# main.net
KiCad netlist of a schematic drawn in EAGLE
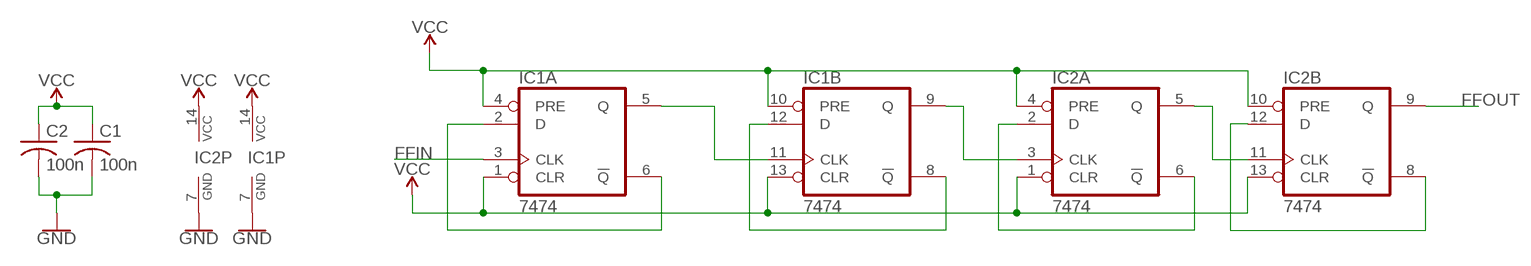
[diagram p0: schematic, sheet 1]

(export (version "E")
  (design (tool "Eeschema 10.0.6"))
  (components
    (comp (ref "C1")
      (value "100n")
      (footprint "eagle-import:C0603")
      (libsource (lib "eagle-import") (part "C-USC0603"))
    )
    (comp (ref "C2")
      (value "100n")
      (footprint "eagle-import:C0603")
      (libsource (lib "eagle-import") (part "C-USC0603"))
    )
    (comp (ref "IC1")
      (value "7474")
      (footprint "eagle-import:TSSOP14")
      (libsource (lib "eagle-import") (part "7474"))
    )
    (comp (ref "IC2")
      (value "7474")
      (footprint "eagle-import:TSSOP14")
      (libsource (lib "eagle-import") (part "7474"))
    )
  )
  (nets
    (net (code "1") (name "/FFIN") (class "Default")
      (node (ref "IC1") (pin "3") (pinfunction "CLK_3") (pintype "input"))
    )
    (net (code "2") (name "/FFOUT") (class "Default")
      (node (ref "IC2") (pin "9") (pinfunction "Q_9") (pintype "output"))
    )
    (net (code "3") (name "GND") (class "Default")
      (node (ref "C1") (pin "2") (pinfunction "2_2") (pintype "passive"))
      (node (ref "C2") (pin "2") (pinfunction "2_2") (pintype "passive"))
      (node (ref "IC1") (pin "7") (pinfunction "GND_7") (pintype "power_in"))
      (node (ref "IC2") (pin "7") (pinfunction "GND_7") (pintype "power_in"))
    )
    (net (code "4") (name "Net-(IC1A-D)") (class "Default")
      (node (ref "IC1") (pin "2") (pinfunction "D_2") (pintype "input"))
      (node (ref "IC1") (pin "6") (pinfunction "~{Q}_6") (pintype "output"))
    )
    (net (code "5") (name "Net-(IC1A-Q)") (class "Default")
      (node (ref "IC1") (pin "11") (pinfunction "CLK_11") (pintype "input"))
      (node (ref "IC1") (pin "5") (pinfunction "Q_5") (pintype "output"))
    )
    (net (code "6") (name "Net-(IC1B-D)") (class "Default")
      (node (ref "IC1") (pin "12") (pinfunction "D_12") (pintype "input"))
      (node (ref "IC1") (pin "8") (pinfunction "~{Q}_8") (pintype "output"))
    )
    (net (code "7") (name "Net-(IC1B-Q)") (class "Default")
      (node (ref "IC1") (pin "9") (pinfunction "Q_9") (pintype "output"))
      (node (ref "IC2") (pin "3") (pinfunction "CLK_3") (pintype "input"))
    )
    (net (code "8") (name "Net-(IC2A-D)") (class "Default")
      (node (ref "IC2") (pin "2") (pinfunction "D_2") (pintype "input"))
      (node (ref "IC2") (pin "6") (pinfunction "~{Q}_6") (pintype "output"))
    )
    (net (code "9") (name "Net-(IC2A-Q)") (class "Default")
      (node (ref "IC2") (pin "11") (pinfunction "CLK_11") (pintype "input"))
      (node (ref "IC2") (pin "5") (pinfunction "Q_5") (pintype "output"))
    )
    (net (code "10") (name "Net-(IC2B-D)") (class "Default")
      (node (ref "IC2") (pin "12") (pinfunction "D_12") (pintype "input"))
      (node (ref "IC2") (pin "8") (pinfunction "~{Q}_8") (pintype "output"))
    )
    (net (code "11") (name "VCC") (class "Default")
      (node (ref "C1") (pin "1") (pinfunction "1_1") (pintype "passive"))
      (node (ref "C2") (pin "1") (pinfunction "1_1") (pintype "passive"))
      (node (ref "IC1") (pin "1") (pinfunction "CLR_1") (pintype "input"))
      (node (ref "IC1") (pin "10") (pinfunction "PRE_10") (pintype "input"))
      (node (ref "IC1") (pin "13") (pinfunction "CLR_13") (pintype "input"))
      (node (ref "IC1") (pin "14") (pinfunction "VCC_14") (pintype "power_in"))
      (node (ref "IC1") (pin "4") (pinfunction "PRE_4") (pintype "input"))
      (node (ref "IC2") (pin "1") (pinfunction "CLR_1") (pintype "input"))
      (node (ref "IC2") (pin "10") (pinfunction "PRE_10") (pintype "input"))
      (node (ref "IC2") (pin "13") (pinfunction "CLR_13") (pintype "input"))
      (node (ref "IC2") (pin "14") (pinfunction "VCC_14") (pintype "power_in"))
      (node (ref "IC2") (pin "4") (pinfunction "PRE_4") (pintype "input"))
    )
  )
)
